# TSE_mother_board_MCU.net
KiCad netlist of a schematic drawn in Altium Designer
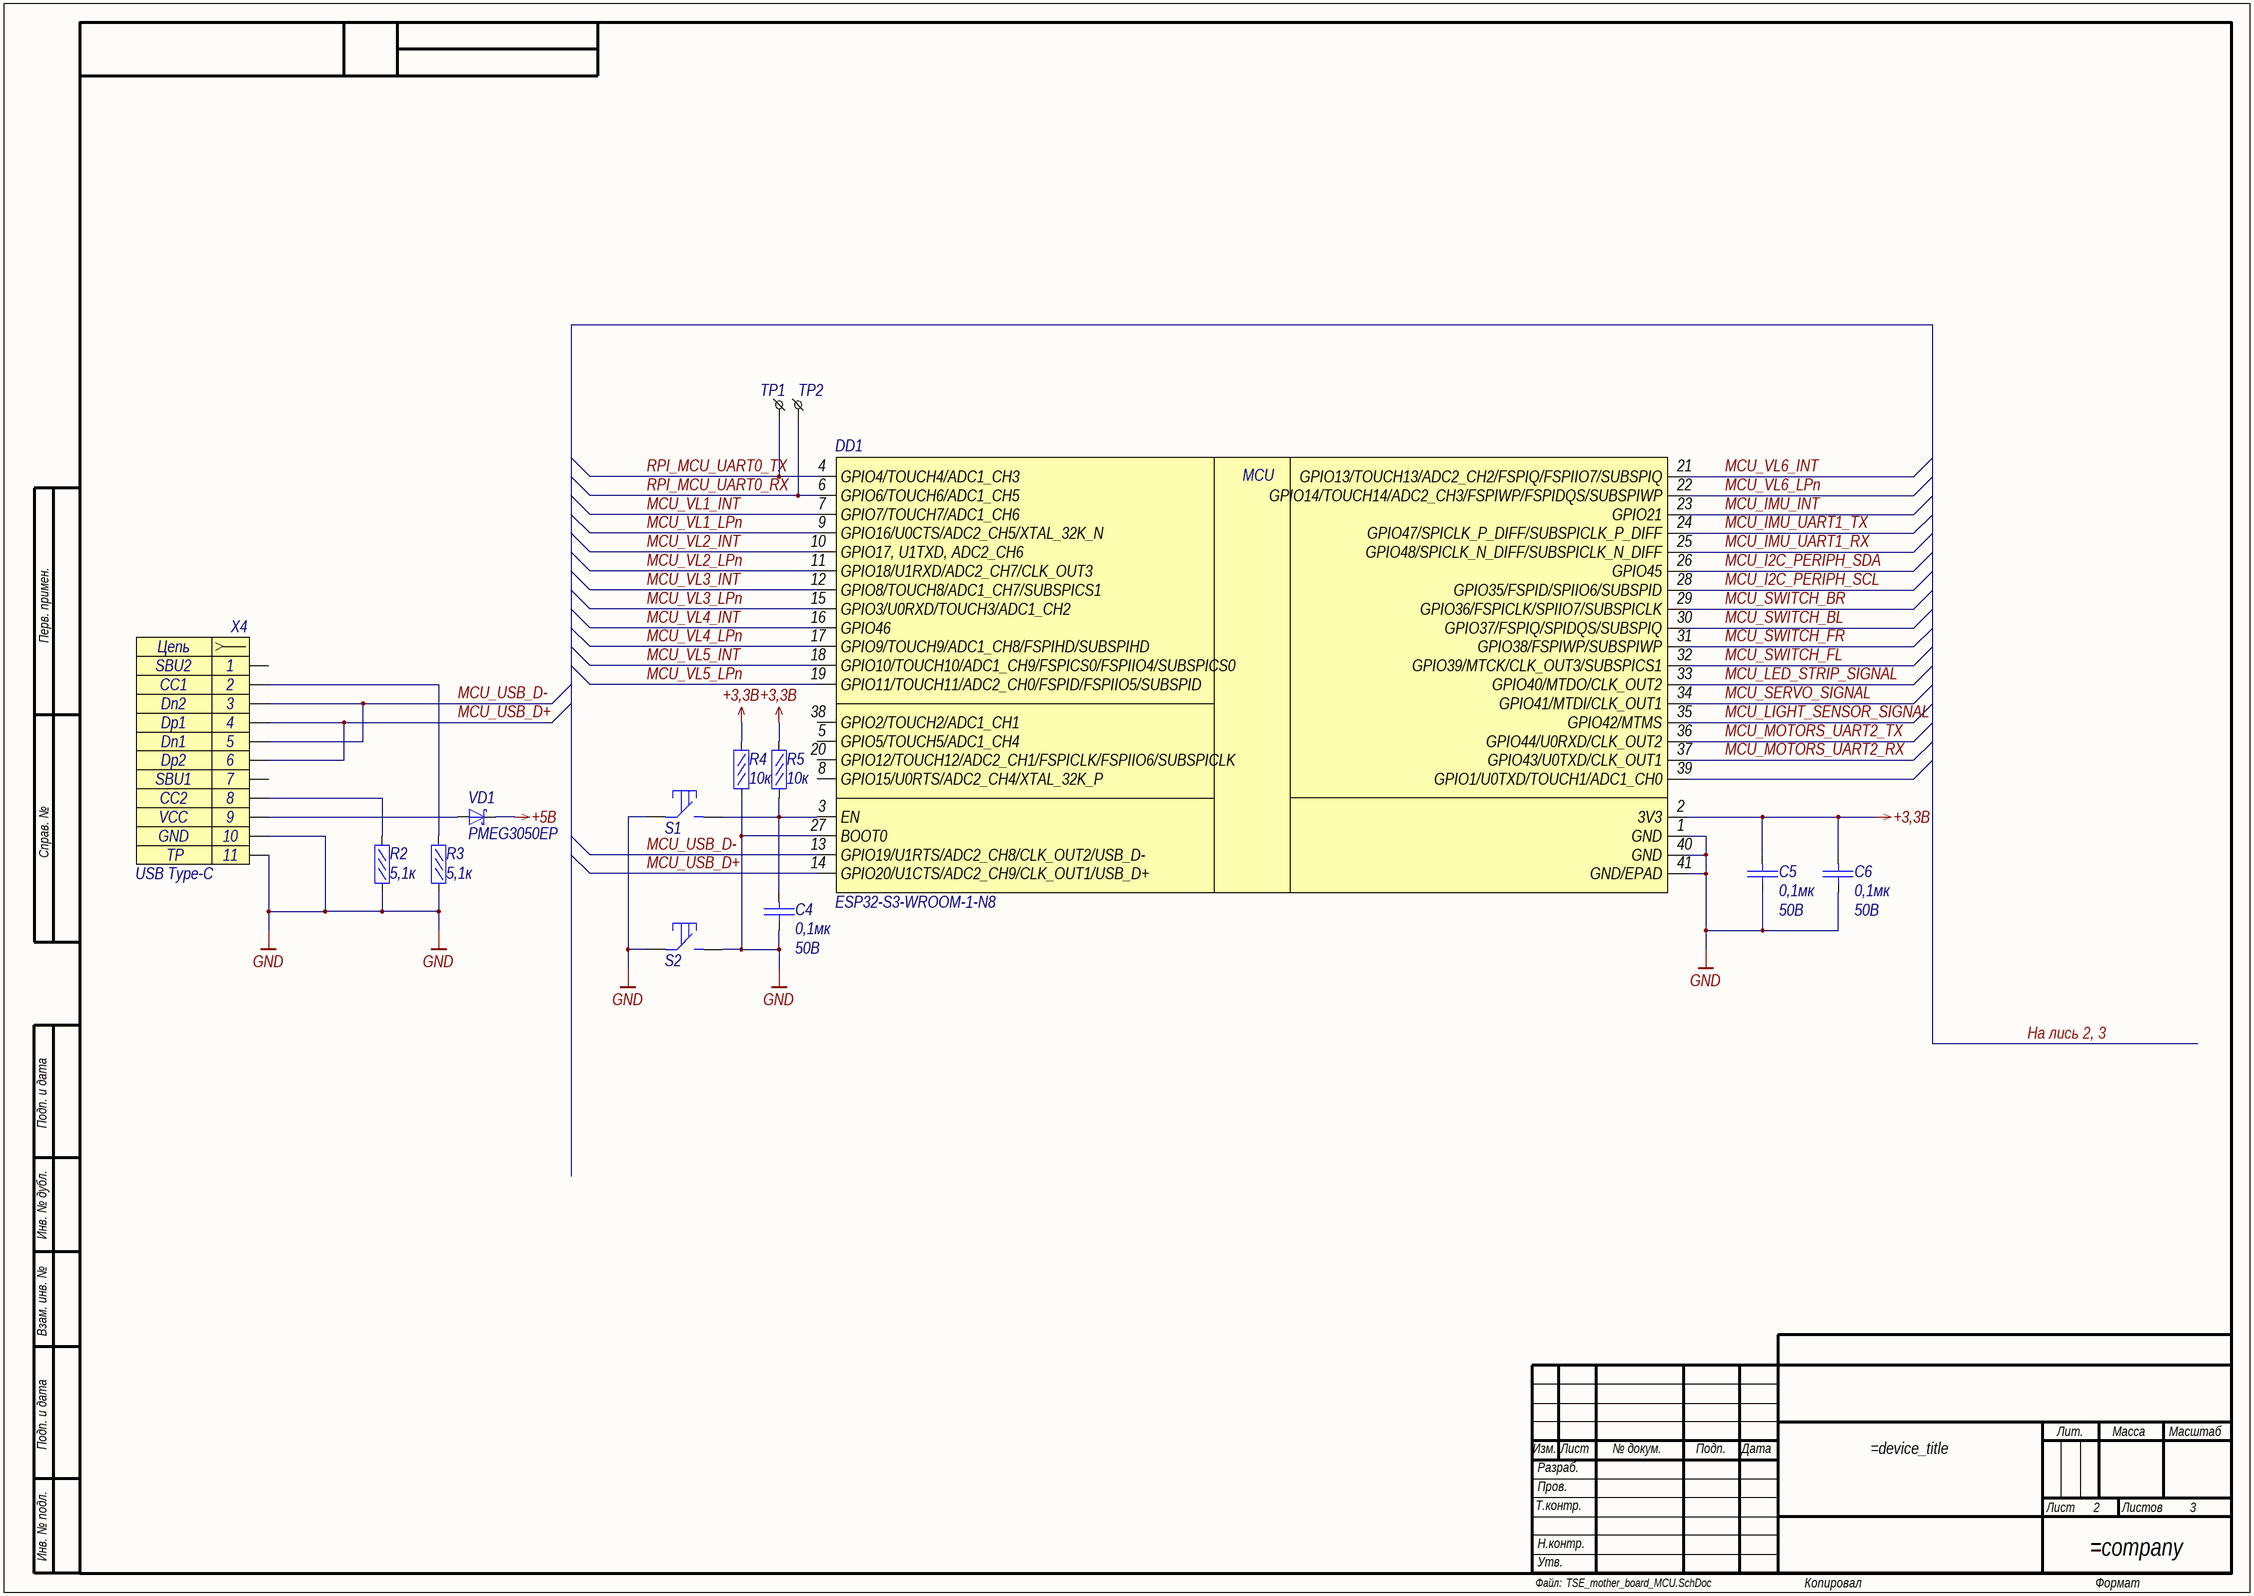
[diagram p0: TSE_mother_board_MCU.SchDoc]

(export (version "E")
  (design (tool "Eeschema 10.0.6"))
  (components
    (comp (ref "C4")
      (value "0,1мк")
      (footprint "C0603")
      (description "Конденсатор кер. 0,1мкФ 50В")
      (fields (field (name "MANUFACTURER") "Yageo") (field (name "VOLTAGE") "50В"))
      (libsource (lib "capacitors") (part "CC0603JPX7R9BB104"))
    )
    (comp (ref "C5")
      (value "0,1мк")
      (footprint "C0603")
      (description "Конденсатор кер. 0,1мкФ 50В")
      (fields (field (name "MANUFACTURER") "Yageo") (field (name "VOLTAGE") "50В"))
      (libsource (lib "capacitors") (part "CC0603JPX7R9BB104"))
    )
    (comp (ref "C6")
      (value "0,1мк")
      (footprint "C0603")
      (description "Конденсатор кер. 0,1мкФ 50В")
      (fields (field (name "MANUFACTURER") "Yageo") (field (name "VOLTAGE") "50В"))
      (libsource (lib "capacitors") (part "CC0603JPX7R9BB104"))
    )
    (comp (ref "DD1")
      (value "ESP32-S3-WROOM-1-N8")
      (footprint "ESP32-S3-WROOM-1")
      (description "Микроконтроллер")
      (libsource (lib "MCU") (part "ESP32-S3-WROOM-1-N8"))
    )
    (comp (ref "R2")
      (value "5,1к")
      (footprint "R0603")
      (description "Резистор 5,1кОм 0,1Вт 1%")
      (fields (field (name "MANUFACTURER") "YAGEO") (field (name "TOLERANCE") "1%"))
      (libsource (lib "resistors") (part "RC0603FR-075K1L"))
    )
    (comp (ref "R3")
      (value "5,1к")
      (footprint "R0603")
      (description "Резистор 5,1кОм 0,1Вт 1%")
      (fields (field (name "MANUFACTURER") "YAGEO") (field (name "TOLERANCE") "1%"))
      (libsource (lib "resistors") (part "RC0603FR-075K1L"))
    )
    (comp (ref "R4")
      (value "10к")
      (footprint "R0603")
      (description "Резистор 10кОм 0,063Вт 1%")
      (fields (field (name "MANUFACTURER") "YAGEO") (field (name "TOLERANCE") "1%"))
      (libsource (lib "resistors") (part "RC0603FR-0710KL"))
    )
    (comp (ref "R5")
      (value "10к")
      (footprint "R0603")
      (description "Резистор 10кОм 0,063Вт 1%")
      (fields (field (name "MANUFACTURER") "YAGEO") (field (name "TOLERANCE") "1%"))
      (libsource (lib "resistors") (part "RC0603FR-0710KL"))
    )
    (comp (ref "S1")
      (value "IT-1187")
      (footprint "SMD button 6x3mm")
      (description "тактовая кнопка SMD")
      (libsource (lib "switches") (part "button"))
    )
    (comp (ref "S2")
      (value "IT-1187")
      (footprint "SMD button 6x3mm")
      (description "тактовая кнопка SMD")
      (libsource (lib "switches") (part "button"))
    )
    (comp (ref "TP1")
      (value "TESTPOINT")
      (footprint "TP_0,6X1")
      (libsource (lib "mount_parts") (part "TESTPOINT_HOLE"))
    )
    (comp (ref "TP2")
      (value "TESTPOINT")
      (footprint "TP_0,6X1")
      (libsource (lib "mount_parts") (part "TESTPOINT_HOLE"))
    )
    (comp (ref "VD1")
      (value "PMEG3050EP")
      (footprint "SOD128")
      (description "Диод Шоттки 30В 5А")
      (fields (field (name "MANUFACTURER") "NXP") (field (name "NAME") "PMEG3050EP"))
      (libsource (lib "diodes") (part "PMEG3050EP_1"))
    )
    (comp (ref "X4")
      (value "USB Type-C")
      (footprint "USB4105-15-A-120")
      (description "USB Type-C USB4105-GF-A / GCT")
      (libsource (lib "headers") (part "USB4105-15-A-120"))
    )
  )
  (nets
    (net (code "1") (name "+3,3В") (class "Default")
      (node (ref "C5") (pin "2") (pinfunction "2_2") (pintype "passive"))
      (node (ref "C6") (pin "2") (pinfunction "2_2") (pintype "passive"))
      (node (ref "DD1") (pin "2") (pinfunction "3V3_2") (pintype "passive"))
      (node (ref "R4") (pin "2") (pinfunction "2_2") (pintype "passive"))
      (node (ref "R5") (pin "2") (pinfunction "2_2") (pintype "passive"))
    )
    (net (code "2") (name "+5В") (class "Default")
      (node (ref "VD1") (pin "1") (pinfunction "K_1") (pintype "passive"))
    )
    (net (code "3") (name "/MCU_I2C_PERIPH_SCL") (class "Default")
      (node (ref "DD1") (pin "28") (pinfunction "GPIO35/FSPID/SPIIO6/SUBSPID_28") (pintype "passive"))
    )
    (net (code "4") (name "/MCU_I2C_PERIPH_SDA") (class "Default")
      (node (ref "DD1") (pin "26") (pinfunction "GPIO45_26") (pintype "passive"))
    )
    (net (code "5") (name "/MCU_IMU_INT") (class "Default")
      (node (ref "DD1") (pin "23") (pinfunction "GPIO21_23") (pintype "passive"))
    )
    (net (code "6") (name "/MCU_IMU_UART1_RX") (class "Default")
      (node (ref "DD1") (pin "25") (pinfunction "GPIO48/SPICLK_N_DIFF/SUBSPICLK_N_DIFF_25") (pintype "passive"))
    )
    (net (code "7") (name "/MCU_IMU_UART1_TX") (class "Default")
      (node (ref "DD1") (pin "24") (pinfunction "GPIO47/SPICLK_P_DIFF/SUBSPICLK_P_DIFF_24") (pintype "passive"))
    )
    (net (code "8") (name "/MCU_LED_STRIP_SIGNAL") (class "Default")
      (node (ref "DD1") (pin "33") (pinfunction "GPIO40/MTDO/CLK_OUT2_33") (pintype "passive"))
    )
    (net (code "9") (name "/MCU_LIGHT_SENSOR_SIGNAL") (class "Default")
      (node (ref "DD1") (pin "35") (pinfunction "GPIO42/MTMS_35") (pintype "passive"))
    )
    (net (code "10") (name "/MCU_MOTORS_UART2_RX") (class "Default")
      (node (ref "DD1") (pin "37") (pinfunction "GPIO43/U0TXD/CLK_OUT1_37") (pintype "passive"))
    )
    (net (code "11") (name "/MCU_MOTORS_UART2_TX") (class "Default")
      (node (ref "DD1") (pin "36") (pinfunction "GPIO44/U0RXD/CLK_OUT2_36") (pintype "passive"))
    )
    (net (code "12") (name "/MCU_SERVO_SIGNAL") (class "Default")
      (node (ref "DD1") (pin "34") (pinfunction "GPIO41/MTDI/CLK_OUT1_34") (pintype "passive"))
    )
    (net (code "13") (name "/MCU_SWITCH_BL") (class "Default")
      (node (ref "DD1") (pin "30") (pinfunction "GPIO37/FSPIQ/SPIDQS/SUBSPIQ_30") (pintype "passive"))
    )
    (net (code "14") (name "/MCU_SWITCH_BR") (class "Default")
      (node (ref "DD1") (pin "29") (pinfunction "GPIO36/FSPICLK/SPIIO7/SUBSPICLK_29") (pintype "passive"))
    )
    (net (code "15") (name "/MCU_SWITCH_FL") (class "Default")
      (node (ref "DD1") (pin "32") (pinfunction "GPIO39/MTCK/CLK_OUT3/SUBSPICS1_32") (pintype "passive"))
    )
    (net (code "16") (name "/MCU_SWITCH_FR") (class "Default")
      (node (ref "DD1") (pin "31") (pinfunction "GPIO38/FSPIWP/SUBSPIWP_31") (pintype "passive"))
    )
    (net (code "17") (name "/MCU_USB_D+") (class "Default")
      (node (ref "DD1") (pin "14") (pinfunction "GPIO20/U1CTS/ADC2_CH9/CLK_OUT1/USB_D+_14") (pintype "passive"))
      (node (ref "X4") (pin "4") (pinfunction "A6_4") (pintype "passive"))
      (node (ref "X4") (pin "6") (pinfunction "B6_6") (pintype "passive"))
    )
    (net (code "18") (name "/MCU_USB_D-") (class "Default")
      (node (ref "DD1") (pin "13") (pinfunction "GPIO19/U1RTS/ADC2_CH8/CLK_OUT2/USB_D-_13") (pintype "passive"))
      (node (ref "X4") (pin "3") (pinfunction "B7_3") (pintype "passive"))
      (node (ref "X4") (pin "5") (pinfunction "A7_5") (pintype "passive"))
    )
    (net (code "19") (name "/MCU_VL1_INT") (class "Default")
      (node (ref "DD1") (pin "7") (pinfunction "GPIO7/TOUCH7/ADC1_CH6_7") (pintype "passive"))
    )
    (net (code "20") (name "/MCU_VL1_LPn") (class "Default")
      (node (ref "DD1") (pin "9") (pinfunction "GPIO16/U0CTS/ADC2_CH5/XTAL_32K_N_9") (pintype "passive"))
    )
    (net (code "21") (name "/MCU_VL2_INT") (class "Default")
      (node (ref "DD1") (pin "10") (pinfunction "GPIO17,_U1TXD,_ADC2_CH6_10") (pintype "passive"))
    )
    (net (code "22") (name "/MCU_VL2_LPn") (class "Default")
      (node (ref "DD1") (pin "11") (pinfunction "GPIO18/U1RXD/ADC2_CH7/CLK_OUT3_11") (pintype "passive"))
    )
    (net (code "23") (name "/MCU_VL3_INT") (class "Default")
      (node (ref "DD1") (pin "12") (pinfunction "GPIO8/TOUCH8/ADC1_CH7/SUBSPICS1_12") (pintype "passive"))
    )
    (net (code "24") (name "/MCU_VL3_LPn") (class "Default")
      (node (ref "DD1") (pin "15") (pinfunction "GPIO3/U0RXD/TOUCH3/ADC1_CH2_15") (pintype "passive"))
    )
    (net (code "25") (name "/MCU_VL4_INT") (class "Default")
      (node (ref "DD1") (pin "16") (pinfunction "GPIO46_16") (pintype "passive"))
    )
    (net (code "26") (name "/MCU_VL4_LPn") (class "Default")
      (node (ref "DD1") (pin "17") (pinfunction "GPIO9/TOUCH9/ADC1_CH8/FSPIHD/SUBSPIHD_17") (pintype "passive"))
    )
    (net (code "27") (name "/MCU_VL5_INT") (class "Default")
      (node (ref "DD1") (pin "18") (pinfunction "GPIO10/TOUCH10/ADC1_CH9/FSPICS0/FSPIIO4/SUBSPICS0_18") (pintype "passive"))
    )
    (net (code "28") (name "/MCU_VL5_LPn") (class "Default")
      (node (ref "DD1") (pin "19") (pinfunction "GPIO11/TOUCH11/ADC2_CH0/FSPID/FSPIIO5/SUBSPID_19") (pintype "passive"))
    )
    (net (code "29") (name "/MCU_VL6_INT") (class "Default")
      (node (ref "DD1") (pin "21") (pinfunction "GPIO13/TOUCH13/ADC2_CH2/FSPIQ/FSPIIO7/SUBSPIQ_21") (pintype "passive"))
    )
    (net (code "30") (name "/MCU_VL6_LPn") (class "Default")
      (node (ref "DD1") (pin "22") (pinfunction "GPIO14/TOUCH14/ADC2_CH3/FSPIWP/FSPIDQS/SUBSPIWP_22") (pintype "passive"))
    )
    (net (code "31") (name "/RPI_MCU_UART0_RX") (class "Default")
      (node (ref "DD1") (pin "6") (pinfunction "GPIO6/TOUCH6/ADC1_CH5_6") (pintype "passive"))
      (node (ref "TP2") (pin "1") (pinfunction "1_1") (pintype "passive"))
    )
    (net (code "32") (name "/RPI_MCU_UART0_TX") (class "Default")
      (node (ref "DD1") (pin "4") (pinfunction "GPIO4/TOUCH4/ADC1_CH3_4") (pintype "passive"))
      (node (ref "TP1") (pin "1") (pinfunction "1_1") (pintype "passive"))
    )
    (net (code "33") (name "GND") (class "Default")
      (node (ref "C4") (pin "1") (pinfunction "1_1") (pintype "passive"))
      (node (ref "C5") (pin "1") (pinfunction "1_1") (pintype "passive"))
      (node (ref "C6") (pin "1") (pinfunction "1_1") (pintype "passive"))
      (node (ref "DD1") (pin "1") (pinfunction "GND_1") (pintype "passive"))
      (node (ref "DD1") (pin "27") (pinfunction "BOOT0_27") (pintype "passive"))
      (node (ref "DD1") (pin "40") (pinfunction "GND_40") (pintype "passive"))
      (node (ref "DD1") (pin "41") (pinfunction "GND/EPAD_41") (pintype "passive"))
      (node (ref "R2") (pin "1") (pinfunction "1_1") (pintype "passive"))
      (node (ref "R3") (pin "1") (pinfunction "1_1") (pintype "passive"))
      (node (ref "R4") (pin "1") (pinfunction "1_1") (pintype "passive"))
      (node (ref "S1") (pin "1") (pinfunction "1_1") (pintype "passive"))
      (node (ref "S2") (pin "1") (pinfunction "1_1") (pintype "passive"))
      (node (ref "S2") (pin "2") (pinfunction "2_2") (pintype "passive"))
      (node (ref "X4") (pin "10") (pinfunction "VCC_10") (pintype "passive"))
      (node (ref "X4") (pin "TP") (pinfunction "TP_TP") (pintype "passive"))
    )
    (net (code "34") (name "Net-(DD1-EN)") (class "Default")
      (node (ref "C4") (pin "2") (pinfunction "2_2") (pintype "passive"))
      (node (ref "DD1") (pin "3") (pinfunction "EN_3") (pintype "passive"))
      (node (ref "R5") (pin "1") (pinfunction "1_1") (pintype "passive"))
      (node (ref "S1") (pin "2") (pinfunction "2_2") (pintype "passive"))
    )
    (net (code "35") (name "Net-(VD1-A)") (class "Default")
      (node (ref "VD1") (pin "2") (pinfunction "A_2") (pintype "passive"))
      (node (ref "X4") (pin "9") (pinfunction "GND_9") (pintype "passive"))
    )
    (net (code "36") (name "Net-(X4-A5)") (class "Default")
      (node (ref "R3") (pin "2") (pinfunction "2_2") (pintype "passive"))
      (node (ref "X4") (pin "2") (pinfunction "A5_2") (pintype "passive"))
    )
    (net (code "37") (name "Net-(X4-B5)") (class "Default")
      (node (ref "R2") (pin "2") (pinfunction "2_2") (pintype "passive"))
      (node (ref "X4") (pin "8") (pinfunction "B5_8") (pintype "passive"))
    )
    (net (code "38") (name "unconnected-(DD1-GPIO1{slash}U0TXD{slash}TOUCH1{slash}ADC1_CH0-Pad39)") (class "Default")
      (node (ref "DD1") (pin "39") (pinfunction "GPIO1/U0TXD/TOUCH1/ADC1_CH0_39") (pintype "passive"))
    )
    (net (code "39") (name "unconnected-(DD1-GPIO2{slash}TOUCH2{slash}ADC1_CH1-Pad38)") (class "Default")
      (node (ref "DD1") (pin "38") (pinfunction "GPIO2/TOUCH2/ADC1_CH1_38") (pintype "passive"))
    )
    (net (code "40") (name "unconnected-(DD1-GPIO5{slash}TOUCH5{slash}ADC1_CH4-Pad5)") (class "Default")
      (node (ref "DD1") (pin "5") (pinfunction "GPIO5/TOUCH5/ADC1_CH4_5") (pintype "passive"))
    )
    (net (code "41") (name "unconnected-(DD1-GPIO12{slash}TOUCH12{slash}ADC2_CH1{slash}FSPICLK{slash}FSPIIO6{slash}SUBSPICLK-Pad20)") (class "Default")
      (node (ref "DD1") (pin "20") (pinfunction "GPIO12/TOUCH12/ADC2_CH1/FSPICLK/FSPIIO6/SUBSPICLK_20") (pintype "passive"))
    )
    (net (code "42") (name "unconnected-(DD1-GPIO15{slash}U0RTS{slash}ADC2_CH4{slash}XTAL_32K_P-Pad8)") (class "Default")
      (node (ref "DD1") (pin "8") (pinfunction "GPIO15/U0RTS/ADC2_CH4/XTAL_32K_P_8") (pintype "passive"))
    )
    (net (code "43") (name "unconnected-(X4-A8-Pad7)") (class "Default")
      (node (ref "X4") (pin "7") (pinfunction "A8_7") (pintype "passive"))
    )
    (net (code "44") (name "unconnected-(X4-B8-Pad1)") (class "Default")
      (node (ref "X4") (pin "1") (pinfunction "B8_1") (pintype "passive"))
    )
  )
)
